# reflow_controller_v2_eagle7.net
KiCad netlist of a schematic drawn in EAGLE
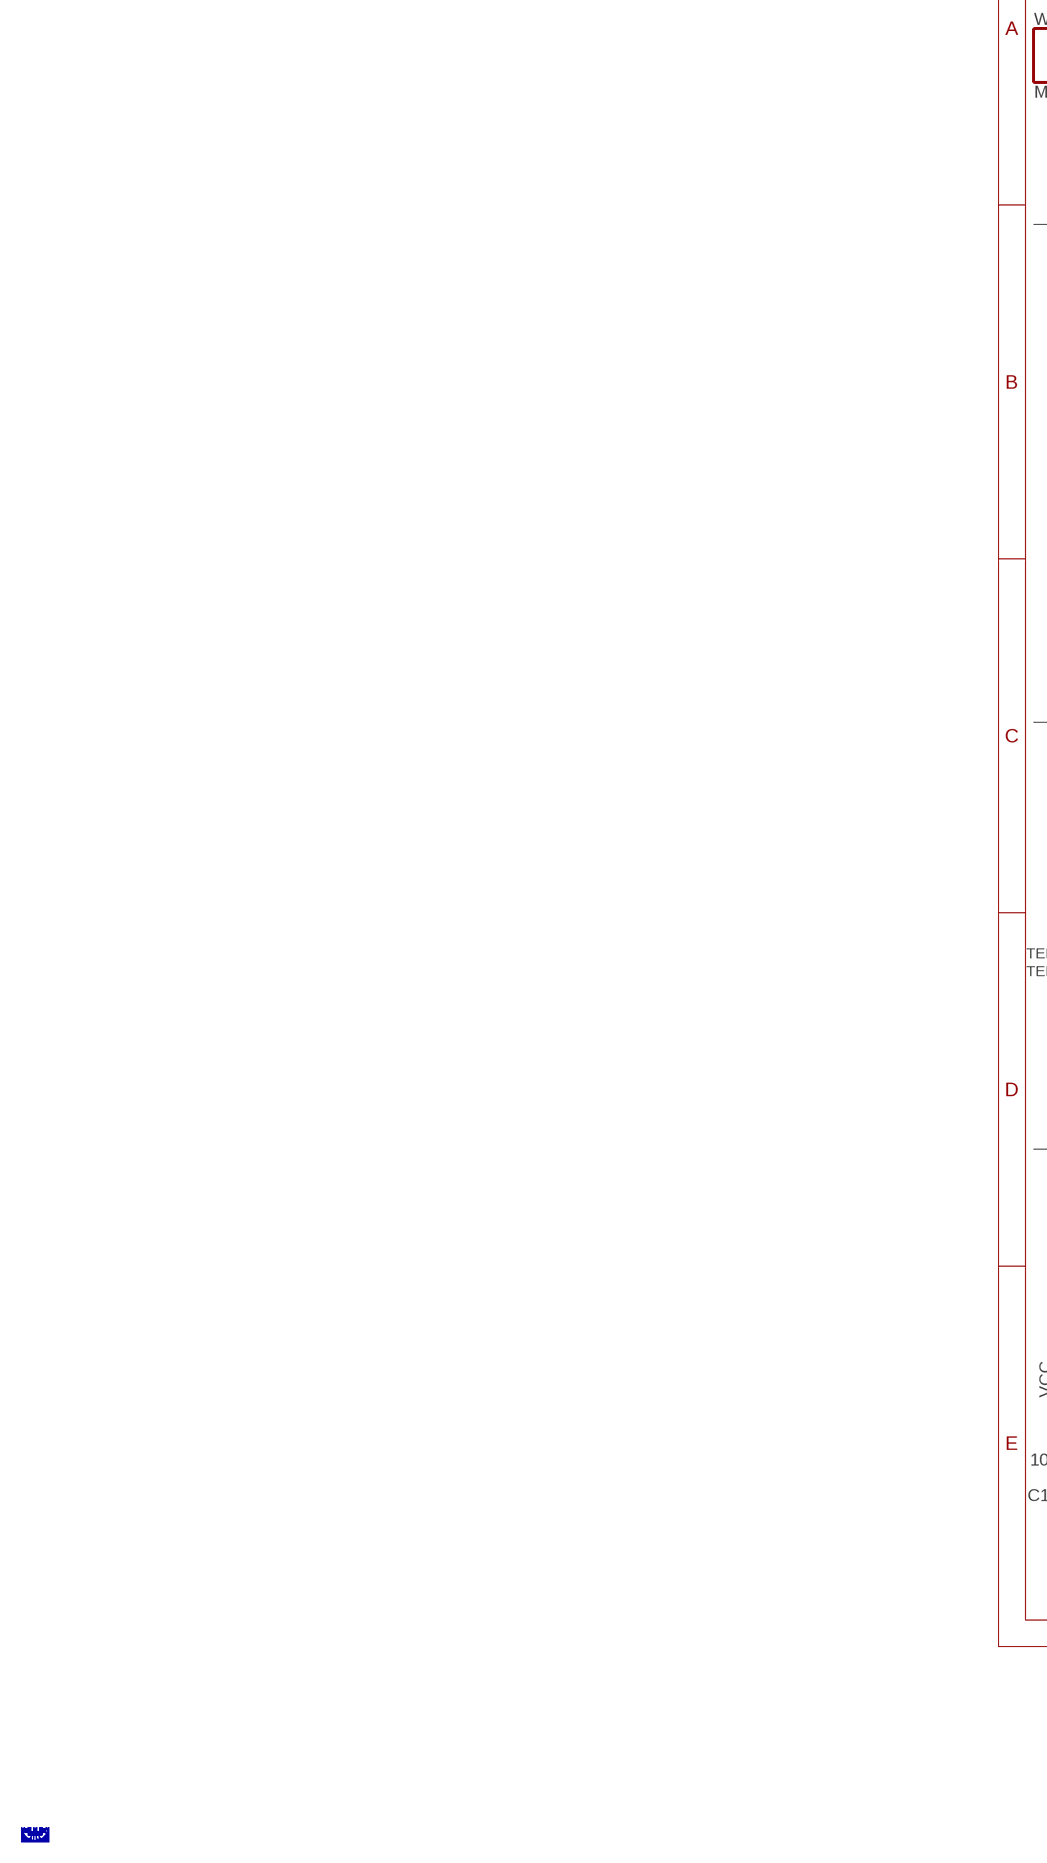
[diagram p0: schematic, sheet 1, part 1 of 2]
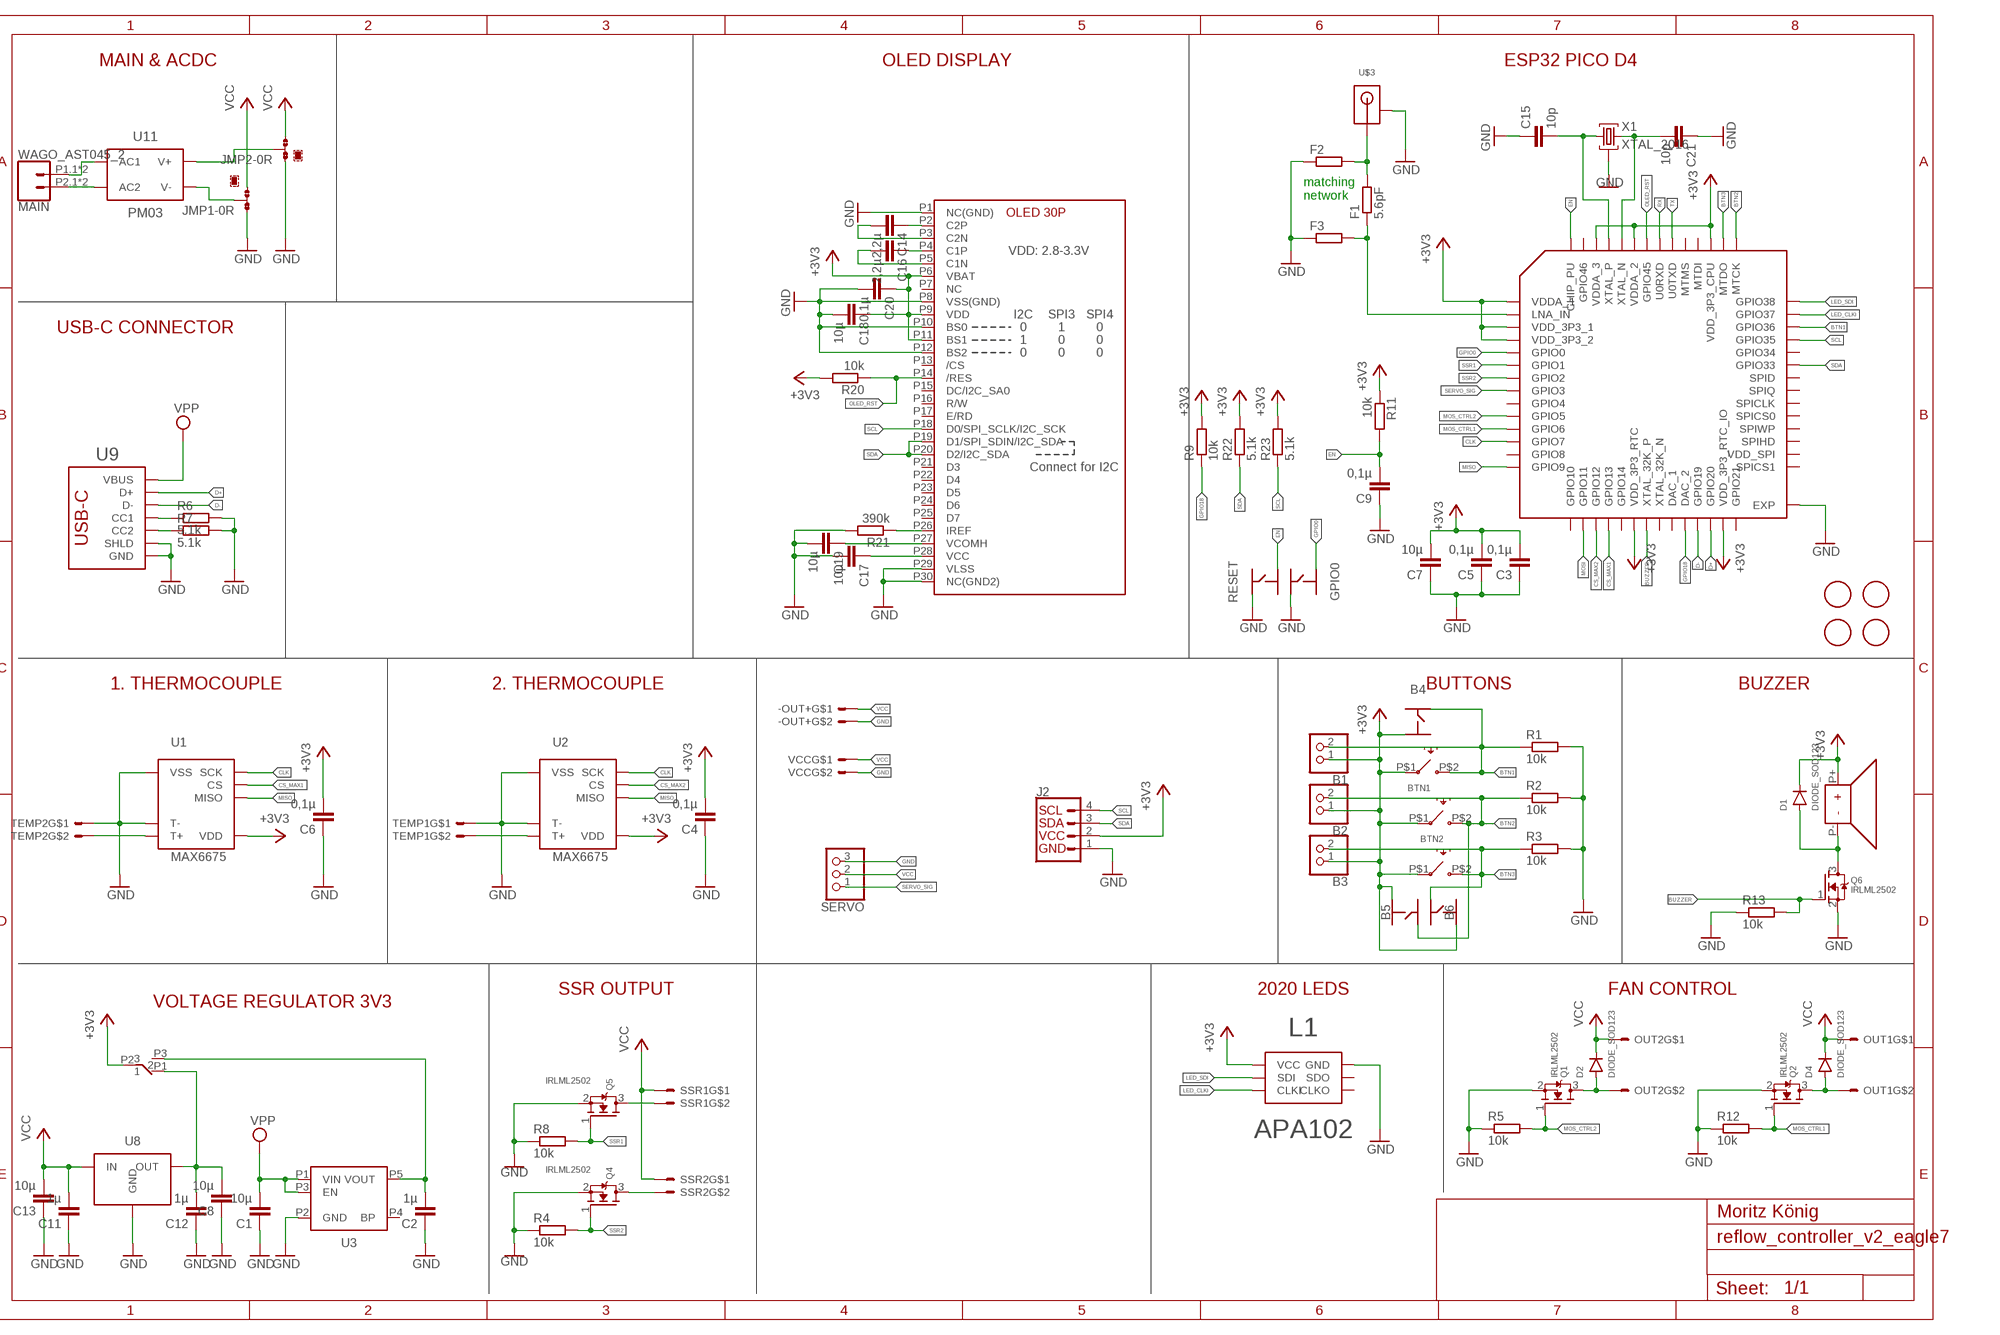
[diagram p1: schematic, sheet 1, part 2 of 2]

(export (version "E")
  (design (tool "Eeschema 10.0.6"))
  (components
    (comp (ref "-OUT+")
      (value "MOLEX_2MM_2P")
      (footprint "eagle-import:MOLEX_2MM_2P")
      (libsource (lib "eagle-import") (part "MOLEX_2MM_2P"))
    )
    (comp (ref "B1")
      (value "PINHD-1X02_2.00")
      (footprint "eagle-import:1X02M")
      (libsource (lib "eagle-import") (part "PINHD-1X02_2.00"))
    )
    (comp (ref "B2")
      (value "PINHD-1X02_2.00")
      (footprint "eagle-import:1X02M")
      (libsource (lib "eagle-import") (part "PINHD-1X02_2.00"))
    )
    (comp (ref "B3")
      (value "PINHD-1X02_2.00")
      (footprint "eagle-import:1X02M")
      (libsource (lib "eagle-import") (part "PINHD-1X02_2.00"))
    )
    (comp (ref "B4")
      (value "BUTTON_4PIN_TS-1070A")
      (footprint "eagle-import:BUTTON_WHITE_SMD")
      (libsource (lib "eagle-import") (part "BUTTON_4PIN_TS-1070A"))
    )
    (comp (ref "B5")
      (value "BUTTON_4PIN_TS-1070A")
      (footprint "eagle-import:BUTTON_WHITE_SMD")
      (libsource (lib "eagle-import") (part "BUTTON_4PIN_TS-1070A"))
    )
    (comp (ref "B6")
      (value "BUTTON_4PIN_TS-1070A")
      (footprint "eagle-import:BUTTON_WHITE_SMD")
      (libsource (lib "eagle-import") (part "BUTTON_4PIN_TS-1070A"))
    )
    (comp (ref "BTN1")
      (value "BUTTON_6X6_SILICON")
      (footprint "eagle-import:BUTTON_SILICON")
      (libsource (lib "eagle-import") (part "BUTTON_6X6_SILICON"))
    )
    (comp (ref "BTN2")
      (value "BUTTON_6X6_SILICON")
      (footprint "eagle-import:BUTTON_SILICON")
      (libsource (lib "eagle-import") (part "BUTTON_6X6_SILICON"))
    )
    (comp (ref "BTN3")
      (value "BUTTON_6X6_SILICON")
      (footprint "eagle-import:BUTTON_SILICON")
      (libsource (lib "eagle-import") (part "BUTTON_6X6_SILICON"))
    )
    (comp (ref "C1")
      (value "10µ")
      (footprint "eagle-import:C0603")
      (libsource (lib "eagle-import") (part "C-EU_WO_KEEPOUT"))
    )
    (comp (ref "C2")
      (value "1µ")
      (footprint "eagle-import:C0603")
      (libsource (lib "eagle-import") (part "C-EU_WO_KEEPOUT"))
    )
    (comp (ref "C3")
      (value "0,1µ")
      (footprint "eagle-import:C0603")
      (libsource (lib "eagle-import") (part "C-EU_WO_KEEPOUT"))
    )
    (comp (ref "C4")
      (value "0,1µ")
      (footprint "eagle-import:C0603")
      (libsource (lib "eagle-import") (part "C-EUC0603"))
    )
    (comp (ref "C5")
      (value "0,1µ")
      (footprint "eagle-import:C0603")
      (libsource (lib "eagle-import") (part "C-EU_WO_KEEPOUT"))
    )
    (comp (ref "C6")
      (value "0,1µ")
      (footprint "eagle-import:C0603")
      (libsource (lib "eagle-import") (part "C-EUC0603"))
    )
    (comp (ref "C7")
      (value "10µ")
      (footprint "eagle-import:C0603")
      (libsource (lib "eagle-import") (part "C-EU_WO_KEEPOUT"))
    )
    (comp (ref "C8")
      (value "10µ")
      (footprint "eagle-import:C0603")
      (libsource (lib "eagle-import") (part "C-EU_WO_KEEPOUT"))
    )
    (comp (ref "C9")
      (value "0,1µ")
      (footprint "eagle-import:C0603")
      (libsource (lib "eagle-import") (part "C-EU_WO_KEEPOUT"))
    )
    (comp (ref "C11")
      (value "1µ")
      (footprint "eagle-import:C0603")
      (libsource (lib "eagle-import") (part "C-EU_WO_KEEPOUT"))
    )
    (comp (ref "C12")
      (value "1µ")
      (footprint "eagle-import:C0603")
      (libsource (lib "eagle-import") (part "C-EU_WO_KEEPOUT"))
    )
    (comp (ref "C13")
      (value "10µ")
      (footprint "eagle-import:C0603")
      (libsource (lib "eagle-import") (part "C-EU_WO_KEEPOUT"))
    )
    (comp (ref "C14")
      (value "2,2µ")
      (footprint "eagle-import:C0603")
      (libsource (lib "eagle-import") (part "C-EU_WO_KEEPOUT"))
    )
    (comp (ref "C15")
      (value "10p")
      (footprint "eagle-import:C0603")
      (libsource (lib "eagle-import") (part "C-EU_WO_KEEPOUT"))
    )
    (comp (ref "C16")
      (value "2,2µ")
      (footprint "eagle-import:C0603")
      (libsource (lib "eagle-import") (part "C-EU_WO_KEEPOUT"))
    )
    (comp (ref "C17")
      (value "10µ")
      (footprint "eagle-import:C0603")
      (libsource (lib "eagle-import") (part "C-EU_WO_KEEPOUT"))
    )
    (comp (ref "C18")
      (value "10µ")
      (footprint "eagle-import:C0603")
      (libsource (lib "eagle-import") (part "C-EU_WO_KEEPOUT"))
    )
    (comp (ref "C19")
      (value "10µ")
      (footprint "eagle-import:C0603")
      (libsource (lib "eagle-import") (part "C-EU_WO_KEEPOUT"))
    )
    (comp (ref "C20")
      (value "0,1µ")
      (footprint "eagle-import:C0603")
      (libsource (lib "eagle-import") (part "C-EU_WO_KEEPOUT"))
    )
    (comp (ref "C21")
      (value "10p")
      (footprint "eagle-import:C0603")
      (libsource (lib "eagle-import") (part "C-EU_WO_KEEPOUT"))
    )
    (comp (ref "D1")
      (value "DIODE_SOD123")
      (footprint "eagle-import:SOD123")
      (libsource (lib "eagle-import") (part "DIODE_SOD123"))
    )
    (comp (ref "D2")
      (value "DIODE_SOD123")
      (footprint "eagle-import:SOD123")
      (libsource (lib "eagle-import") (part "DIODE_SOD123"))
    )
    (comp (ref "D4")
      (value "DIODE_SOD123")
      (footprint "eagle-import:SOD123")
      (libsource (lib "eagle-import") (part "DIODE_SOD123"))
    )
    (comp (ref "ESP")
      (value "ESP32_S2_QFN56_NEW")
      (footprint "eagle-import:QFN56_7X7")
      (libsource (lib "eagle-import") (part "ESP32_S2_QFN56_NEW"))
    )
    (comp (ref "F1")
      (value "5.6pF")
      (footprint "eagle-import:R0402")
      (libsource (lib "eagle-import") (part "R-EU-0402-WOKEEPOUT"))
    )
    (comp (ref "F2")
      (value "R-EU-0402-WOKEEPOUT")
      (footprint "eagle-import:R0402")
      (libsource (lib "eagle-import") (part "R-EU-0402-WOKEEPOUT"))
    )
    (comp (ref "F3")
      (value "R-EU-0402-WOKEEPOUT")
      (footprint "eagle-import:R0402")
      (libsource (lib "eagle-import") (part "R-EU-0402-WOKEEPOUT"))
    )
    (comp (ref "GPIO0")
      (value "BUTTON_4PIN_TS_1177")
      (footprint "eagle-import:TS-1177-C-B-B")
      (libsource (lib "eagle-import") (part "BUTTON_4PIN_TS_1177"))
    )
    (comp (ref "J2")
      (value "QWIIC_CONNECTORJS-1MM")
      (footprint "eagle-import:1X04_1MM_RA")
      (libsource (lib "eagle-import") (part "QWIIC_CONNECTORJS-1MM"))
    )
    (comp (ref "JMP1")
      (value "0R-JUMPA")
      (footprint "eagle-import:A0R-JMP")
      (libsource (lib "eagle-import") (part "0R-JUMPA"))
    )
    (comp (ref "JMP2")
      (value "0R-JUMPA")
      (footprint "eagle-import:A0R-JMP")
      (libsource (lib "eagle-import") (part "0R-JUMPA"))
    )
    (comp (ref "L1")
      (value "APA102_2020")
      (footprint "eagle-import:APA102_2020")
      (libsource (lib "eagle-import") (part "APA102_2020"))
    )
    (comp (ref "MAIN")
      (value "WAGO_AST045_2")
      (footprint "eagle-import:WAGO_AST045_2")
      (libsource (lib "eagle-import") (part "WAGO_AST045_2"))
    )
    (comp (ref "OUT1")
      (value "MOLEX_2MM_2P")
      (footprint "eagle-import:MOLEX_2MM_2P")
      (libsource (lib "eagle-import") (part "MOLEX_2MM_2P"))
    )
    (comp (ref "OUT2")
      (value "MOLEX_2MM_2P")
      (footprint "eagle-import:MOLEX_2MM_2P")
      (libsource (lib "eagle-import") (part "MOLEX_2MM_2P"))
    )
    (comp (ref "Q1")
      (value "IRLML2502")
      (footprint "eagle-import:SOT23")
      (libsource (lib "eagle-import") (part "IRLML2502"))
    )
    (comp (ref "Q2")
      (value "IRLML2502")
      (footprint "eagle-import:SOT23")
      (libsource (lib "eagle-import") (part "IRLML2502"))
    )
    (comp (ref "Q4")
      (value "IRLML2502")
      (footprint "eagle-import:SOT23")
      (libsource (lib "eagle-import") (part "IRLML2502"))
    )
    (comp (ref "Q5")
      (value "IRLML2502")
      (footprint "eagle-import:SOT23")
      (libsource (lib "eagle-import") (part "IRLML2502"))
    )
    (comp (ref "Q6")
      (value "IRLML2502")
      (footprint "eagle-import:SOT23")
      (libsource (lib "eagle-import") (part "IRLML2502"))
    )
    (comp (ref "R1")
      (value "10k")
      (footprint "eagle-import:R0603")
      (libsource (lib "eagle-import") (part "R-EU_WO_KEEPOUT"))
    )
    (comp (ref "R2")
      (value "10k")
      (footprint "eagle-import:R0603")
      (libsource (lib "eagle-import") (part "R-EU_WO_KEEPOUT"))
    )
    (comp (ref "R3")
      (value "10k")
      (footprint "eagle-import:R0603")
      (libsource (lib "eagle-import") (part "R-EU_WO_KEEPOUT"))
    )
    (comp (ref "R4")
      (value "10k")
      (footprint "eagle-import:R0603")
      (libsource (lib "eagle-import") (part "R-EU_WO_KEEPOUT"))
    )
    (comp (ref "R5")
      (value "10k")
      (footprint "eagle-import:R0603")
      (libsource (lib "eagle-import") (part "R-EU_WO_KEEPOUT"))
    )
    (comp (ref "R6")
      (value "5.1k")
      (footprint "eagle-import:R0603")
      (libsource (lib "eagle-import") (part "R-EU_WO_KEEPOUT"))
    )
    (comp (ref "R7")
      (value "5.1k")
      (footprint "eagle-import:R0603")
      (libsource (lib "eagle-import") (part "R-EU_WO_KEEPOUT"))
    )
    (comp (ref "R8")
      (value "10k")
      (footprint "eagle-import:R0603")
      (libsource (lib "eagle-import") (part "R-EU_WO_KEEPOUT"))
    )
    (comp (ref "R9")
      (value "10k")
      (footprint "eagle-import:R0603")
      (libsource (lib "eagle-import") (part "R-EU_WO_KEEPOUT"))
    )
    (comp (ref "R11")
      (value "10k")
      (footprint "eagle-import:R0603")
      (libsource (lib "eagle-import") (part "R-EU_WO_KEEPOUT"))
    )
    (comp (ref "R12")
      (value "10k")
      (footprint "eagle-import:R0603")
      (libsource (lib "eagle-import") (part "R-EU_WO_KEEPOUT"))
    )
    (comp (ref "R13")
      (value "10k")
      (footprint "eagle-import:R0603")
      (libsource (lib "eagle-import") (part "R-EU_WO_KEEPOUT"))
    )
    (comp (ref "R20")
      (value "10k")
      (footprint "eagle-import:R0603")
      (libsource (lib "eagle-import") (part "R-EU_WO_KEEPOUT"))
    )
    (comp (ref "R21")
      (value "390k")
      (footprint "eagle-import:R0603")
      (libsource (lib "eagle-import") (part "R-EU_WO_KEEPOUT"))
    )
    (comp (ref "R22")
      (value "5.1k")
      (footprint "eagle-import:R0603")
      (libsource (lib "eagle-import") (part "R-EU_WO_KEEPOUT"))
    )
    (comp (ref "R23")
      (value "5.1k")
      (footprint "eagle-import:R0603")
      (libsource (lib "eagle-import") (part "R-EU_WO_KEEPOUT"))
    )
    (comp (ref "RESET")
      (value "BUTTON_4PIN_TS_1177")
      (footprint "eagle-import:TS-1177-C-B-B")
      (libsource (lib "eagle-import") (part "BUTTON_4PIN_TS_1177"))
    )
    (comp (ref "S1")
      (value "SWITCH_MS-22C01-G010")
      (footprint "eagle-import:MS-22C01-G010")
      (libsource (lib "eagle-import") (part "SWITCH_MS-22C01-G010"))
    )
    (comp (ref "SERVO")
      (value "PINHD-1X03_2.54")
      (footprint "eagle-import:1X03")
      (libsource (lib "eagle-import") (part "PINHD-1X03_2.54"))
    )
    (comp (ref "SSR1")
      (value "MOLEX_2MM_2P")
      (footprint "eagle-import:MOLEX_2MM_2P")
      (libsource (lib "eagle-import") (part "MOLEX_2MM_2P"))
    )
    (comp (ref "SSR2")
      (value "MOLEX_2MM_2P")
      (footprint "eagle-import:MOLEX_2MM_2P")
      (libsource (lib "eagle-import") (part "MOLEX_2MM_2P"))
    )
    (comp (ref "TEMP1")
      (value "MOLEX_2MM_2P")
      (footprint "eagle-import:MOLEX_2MM_2P")
      (libsource (lib "eagle-import") (part "MOLEX_2MM_2P"))
    )
    (comp (ref "TEMP2")
      (value "MOLEX_2MM_2P")
      (footprint "eagle-import:MOLEX_2MM_2P")
      (libsource (lib "eagle-import") (part "MOLEX_2MM_2P"))
    )
    (comp (ref "U$1")
      (value "FIDUCIAL")
      (footprint "eagle-import:FIDUCIAL_1MM")
      (libsource (lib "eagle-import") (part "FIDUCIAL"))
    )
    (comp (ref "U$2")
      (value "FIDUCIAL")
      (footprint "eagle-import:FIDUCIAL_1MM")
      (libsource (lib "eagle-import") (part "FIDUCIAL"))
    )
    (comp (ref "U$3")
      (value "UFL_ANT_CONNECTOR")
      (footprint "eagle-import:UFL_ANT_CONNECTOR")
      (libsource (lib "eagle-import") (part "UFL_ANT_CONNECTOR"))
    )
    (comp (ref "U$4")
      (value "FIDUCIAL")
      (footprint "eagle-import:FIDUCIAL_1MM")
      (libsource (lib "eagle-import") (part "FIDUCIAL"))
    )
    (comp (ref "U$5")
      (value "FIDUCIAL")
      (footprint "eagle-import:FIDUCIAL_1MM")
      (libsource (lib "eagle-import") (part "FIDUCIAL"))
    )
    (comp (ref "U1")
      (value "MAX6675")
      (footprint "eagle-import:SO8")
      (libsource (lib "eagle-import") (part "MAX6675"))
    )
    (comp (ref "U2")
      (value "MAX6675")
      (footprint "eagle-import:SO8")
      (libsource (lib "eagle-import") (part "MAX6675"))
    )
    (comp (ref "U3")
      (value "RT9193_SC70-5")
      (footprint "eagle-import:SC-70-5")
      (libsource (lib "eagle-import") (part "RT9193_SC70-5"))
    )
    (comp (ref "U4")
      (value "OLD_096_SSD1306_30P_2B")
      (footprint "eagle-import:OLED_096_30P_B")
      (libsource (lib "eagle-import") (part "OLD_096_SSD1306_30P_2B"))
    )
    (comp (ref "U8")
      (value "LM1117")
      (footprint "eagle-import:SOT223")
      (libsource (lib "eagle-import") (part "LM1117"))
    )
    (comp (ref "U9")
      (value "USB_C_C393939")
      (footprint "eagle-import:USBC_C393939")
      (libsource (lib "eagle-import") (part "USB_C_C393939"))
    )
    (comp (ref "U10")
      (value "MLT-5030-BUZZER")
      (footprint "eagle-import:MLT-5030-BUZZER")
      (libsource (lib "eagle-import") (part "MLT-5030-BUZZER"))
    )
    (comp (ref "U11")
      (value "HILINK_PM03")
      (footprint "eagle-import:HILINK_PM03")
      (libsource (lib "eagle-import") (part "HILINK_PM03"))
    )
    (comp (ref "VCC")
      (value "MOLEX_2MM_2P")
      (footprint "eagle-import:MOLEX_2MM_2P")
      (libsource (lib "eagle-import") (part "MOLEX_2MM_2P"))
    )
    (comp (ref "X1")
      (value "XTAL_2016")
      (footprint "eagle-import:XTYL_2016")
      (libsource (lib "eagle-import") (part "XTAL_2016"))
    )
  )
  (nets
    (net (code "1") (name "+3V3") (class "Default")
      (node (ref "B1") (pin "1") (pinfunction "1_1") (pintype "passive"))
      (node (ref "B2") (pin "1") (pinfunction "1_1") (pintype "passive"))
      (node (ref "B3") (pin "1") (pinfunction "1_1") (pintype "passive"))
      (node (ref "B4") (pin "P$2") (pinfunction "3_P$2") (pintype "bidirectional"))
      (node (ref "B5") (pin "P$2") (pinfunction "3_P$2") (pintype "bidirectional"))
      (node (ref "B6") (pin "P$2") (pinfunction "3_P$2") (pintype "bidirectional"))
      (node (ref "BTN1") (pin "P$1") (pinfunction "P1_P$1") (pintype "bidirectional"))
      (node (ref "BTN2") (pin "P$1") (pinfunction "P1_P$1") (pintype "bidirectional"))
      (node (ref "BTN3") (pin "P$1") (pinfunction "P1_P$1") (pintype "bidirectional"))
      (node (ref "C18") (pin "1") (pinfunction "1_1") (pintype "passive"))
      (node (ref "C20") (pin "1") (pinfunction "1_1") (pintype "passive"))
      (node (ref "C3") (pin "2") (pinfunction "2_2") (pintype "passive"))
      (node (ref "C4") (pin "2") (pinfunction "2_2") (pintype "passive"))
      (node (ref "C5") (pin "2") (pinfunction "2_2") (pintype "passive"))
      (node (ref "C6") (pin "2") (pinfunction "2_2") (pintype "passive"))
      (node (ref "C7") (pin "2") (pinfunction "2_2") (pintype "passive"))
      (node (ref "D1") (pin "P$2") (pinfunction "C_P$2") (pintype "passive"))
      (node (ref "ESP") (pin "1") (pinfunction "VDDA_1_1") (pintype "bidirectional"))
      (node (ref "ESP") (pin "20") (pinfunction "VDD_3P3_RTC_20") (pintype "bidirectional"))
      (node (ref "ESP") (pin "27") (pinfunction "VDD_3P3_RTC_IO_27") (pintype "bidirectional"))
      (node (ref "ESP") (pin "3") (pinfunction "VDD_3P3_1_3") (pintype "bidirectional"))
      (node (ref "ESP") (pin "4") (pinfunction "VDD_3P3_2_4") (pintype "bidirectional"))
      (node (ref "ESP") (pin "45") (pinfunction "VDD_3P3_CPU_45") (pintype "bidirectional"))
      (node (ref "ESP") (pin "51") (pinfunction "VDDA_2_51") (pintype "bidirectional"))
      (node (ref "ESP") (pin "54") (pinfunction "VDDA_3_54") (pintype "bidirectional"))
      (node (ref "J2") (pin "2") (pinfunction "VCC_2") (pintype "power_in"))
      (node (ref "L1") (pin "P1") (pinfunction "VCC_P1") (pintype "bidirectional"))
      (node (ref "L1") (pin "P1.1") (pinfunction "VCC_P1.1") (pintype "bidirectional"))
      (node (ref "R11") (pin "1") (pinfunction "1_1") (pintype "passive"))
      (node (ref "R20") (pin "2") (pinfunction "2_2") (pintype "passive"))
      (node (ref "R22") (pin "2") (pinfunction "2_2") (pintype "passive"))
      (node (ref "R23") (pin "2") (pinfunction "2_2") (pintype "passive"))
      (node (ref "R9") (pin "2") (pinfunction "2_2") (pintype "passive"))
      (node (ref "S1") (pin "P2") (pinfunction "2_P2") (pintype "bidirectional"))
      (node (ref "U1") (pin "4") (pinfunction "VDD_4") (pintype "bidirectional"))
      (node (ref "U10") (pin "P+") (pinfunction "P+_P+") (pintype "bidirectional"))
      (node (ref "U2") (pin "4") (pinfunction "VDD_4") (pintype "bidirectional"))
      (node (ref "U4") (pin "P11") (pinfunction "BS1_P11") (pintype "bidirectional"))
      (node (ref "U4") (pin "P6") (pinfunction "VBAT_P6") (pintype "bidirectional"))
      (node (ref "U4") (pin "P9") (pinfunction "VDD_P9") (pintype "bidirectional"))
    )
    (net (code "2") (name "BTN1") (class "Default")
      (node (ref "B1") (pin "2") (pinfunction "2_2") (pintype "passive"))
      (node (ref "B4") (pin "P$4") (pinfunction "2_P$4") (pintype "bidirectional"))
      (node (ref "BTN1") (pin "P$2") (pinfunction "P2_P$2") (pintype "bidirectional"))
      (node (ref "ESP") (pin "40") (pinfunction "GPIO36_40") (pintype "bidirectional"))
      (node (ref "R1") (pin "1") (pinfunction "1_1") (pintype "passive"))
    )
    (net (code "3") (name "BTN2") (class "Default")
      (node (ref "B2") (pin "2") (pinfunction "2_2") (pintype "passive"))
      (node (ref "B5") (pin "P$4") (pinfunction "2_P$4") (pintype "bidirectional"))
      (node (ref "BTN2") (pin "P$2") (pinfunction "P2_P$2") (pintype "bidirectional"))
      (node (ref "ESP") (pin "43") (pinfunction "MTCK_43") (pintype "bidirectional"))
      (node (ref "R2") (pin "1") (pinfunction "1_1") (pintype "passive"))
    )
    (net (code "4") (name "BTN3") (class "Default")
      (node (ref "B3") (pin "2") (pinfunction "2_2") (pintype "passive"))
      (node (ref "B6") (pin "P$4") (pinfunction "2_P$4") (pintype "bidirectional"))
      (node (ref "BTN3") (pin "P$2") (pinfunction "P2_P$2") (pintype "bidirectional"))
      (node (ref "ESP") (pin "44") (pinfunction "MTDO_44") (pintype "bidirectional"))
      (node (ref "R3") (pin "1") (pinfunction "1_1") (pintype "passive"))
    )
    (net (code "5") (name "BUZZER") (class "Default")
      (node (ref "ESP") (pin "21") (pinfunction "XTAL_32K_P_21") (pintype "bidirectional"))
      (node (ref "Q6") (pin "1") (pinfunction "G_1") (pintype "bidirectional"))
      (node (ref "R13") (pin "2") (pinfunction "2_2") (pintype "passive"))
    )
    (net (code "6") (name "CLK") (class "Default")
      (node (ref "ESP") (pin "12") (pinfunction "GPIO7_12") (pintype "bidirectional"))
      (node (ref "U1") (pin "5") (pinfunction "SCK_5") (pintype "bidirectional"))
      (node (ref "U2") (pin "5") (pinfunction "SCK_5") (pintype "bidirectional"))
    )
    (net (code "7") (name "CS_MAX1") (class "Default")
      (node (ref "ESP") (pin "18") (pinfunction "GPIO13_18") (pintype "bidirectional"))
      (node (ref "U1") (pin "6") (pinfunction "CS_6") (pintype "bidirectional"))
    )
    (net (code "8") (name "CS_MAX2") (class "Default")
      (node (ref "ESP") (pin "17") (pinfunction "GPIO12_17") (pintype "bidirectional"))
      (node (ref "U2") (pin "6") (pinfunction "CS_6") (pintype "bidirectional"))
    )
    (net (code "9") (name "D+") (class "Default")
      (node (ref "ESP") (pin "26") (pinfunction "GPIO20_26") (pintype "bidirectional"))
      (node (ref "U9") (pin "A6") (pinfunction "D+_A6") (pintype "bidirectional"))
      (node (ref "U9") (pin "B6") (pinfunction "D+_B6") (pintype "bidirectional"))
    )
    (net (code "10") (name "D-") (class "Default")
      (node (ref "ESP") (pin "25") (pinfunction "GPIO19_25") (pintype "bidirectional"))
      (node (ref "U9") (pin "A7") (pinfunction "D-_A7") (pintype "bidirectional"))
      (node (ref "U9") (pin "B7") (pinfunction "D-_B7") (pintype "bidirectional"))
    )
    (net (code "11") (name "EN") (class "Default")
      (node (ref "C9") (pin "2") (pinfunction "2_2") (pintype "passive"))
      (node (ref "ESP") (pin "56") (pinfunction "CHIP_PU_56") (pintype "bidirectional"))
      (node (ref "R11") (pin "2") (pinfunction "2_2") (pintype "passive"))
      (node (ref "RESET") (pin "P4") (pinfunction "4_P4") (pintype "bidirectional"))
    )
    (net (code "12") (name "GND") (class "Default")
      (node (ref "-OUT+") (pin "2") (pinfunction "S_2") (pintype "passive"))
      (node (ref "C1") (pin "1") (pinfunction "1_1") (pintype "passive"))
      (node (ref "C11") (pin "1") (pinfunction "1_1") (pintype "passive"))
      (node (ref "C12") (pin "1") (pinfunction "1_1") (pintype "passive"))
      (node (ref "C13") (pin "1") (pinfunction "1_1") (pintype "passive"))
      (node (ref "C15") (pin "1") (pinfunction "1_1") (pintype "passive"))
      (node (ref "C17") (pin "2") (pinfunction "2_2") (pintype "passive"))
      (node (ref "C18") (pin "2") (pinfunction "2_2") (pintype "passive"))
      (node (ref "C19") (pin "2") (pinfunction "2_2") (pintype "passive"))
      (node (ref "C2") (pin "1") (pinfunction "1_1") (pintype "passive"))
      (node (ref "C20") (pin "2") (pinfunction "2_2") (pintype "passive"))
      (node (ref "C21") (pin "1") (pinfunction "1_1") (pintype "passive"))
      (node (ref "C3") (pin "1") (pinfunction "1_1") (pintype "passive"))
      (node (ref "C4") (pin "1") (pinfunction "1_1") (pintype "passive"))
      (node (ref "C5") (pin "1") (pinfunction "1_1") (pintype "passive"))
      (node (ref "C6") (pin "1") (pinfunction "1_1") (pintype "passive"))
      (node (ref "C7") (pin "1") (pinfunction "1_1") (pintype "passive"))
      (node (ref "C8") (pin "1") (pinfunction "1_1") (pintype "passive"))
      (node (ref "C9") (pin "1") (pinfunction "1_1") (pintype "passive"))
      (node (ref "ESP") (pin "57") (pinfunction "EXP_57") (pintype "bidirectional"))
      (node (ref "F2") (pin "1") (pinfunction "1_1") (pintype "passive"))
      (node (ref "F3") (pin "1") (pinfunction "1_1") (pintype "passive"))
      (node (ref "GPIO0") (pin "P1") (pinfunction "1_P1") (pintype "bidirectional"))
      (node (ref "J2") (pin "1") (pinfunction "GND_1") (pintype "power_in"))
      (node (ref "JMP1") (pin "1") (pinfunction "1_1") (pintype "passive"))
      (node (ref "JMP2") (pin "1") (pinfunction "1_1") (pintype "passive"))
      (node (ref "L1") (pin "P6") (pinfunction "GND_P6") (pintype "bidirectional"))
      (node (ref "L1") (pin "P6.1") (pinfunction "GND_P6.1") (pintype "bidirectional"))
      (node (ref "Q1") (pin "2") (pinfunction "S_2") (pintype "bidirectional"))
      (node (ref "Q2") (pin "2") (pinfunction "S_2") (pintype "bidirectional"))
      (node (ref "Q4") (pin "2") (pinfunction "S_2") (pintype "bidirectional"))
      (node (ref "Q5") (pin "2") (pinfunction "S_2") (pintype "bidirectional"))
      (node (ref "Q6") (pin "2") (pinfunction "S_2") (pintype "bidirectional"))
      (node (ref "R1") (pin "2") (pinfunction "2_2") (pintype "passive"))
      (node (ref "R12") (pin "1") (pinfunction "1_1") (pintype "passive"))
      (node (ref "R13") (pin "1") (pinfunction "1_1") (pintype "passive"))
      (node (ref "R2") (pin "2") (pinfunction "2_2") (pintype "passive"))
      (node (ref "R21") (pin "2") (pinfunction "2_2") (pintype "passive"))
      (node (ref "R3") (pin "2") (pinfunction "2_2") (pintype "passive"))
      (node (ref "R4") (pin "1") (pinfunction "1_1") (pintype "passive"))
      (node (ref "R5") (pin "1") (pinfunction "1_1") (pintype "passive"))
      (node (ref "R6") (pin "2") (pinfunction "2_2") (pintype "passive"))
      (node (ref "R7") (pin "2") (pinfunction "2_2") (pintype "passive"))
      (node (ref "R8") (pin "1") (pinfunction "1_1") (pintype "passive"))
      (node (ref "RESET") (pin "P1") (pinfunction "1_P1") (pintype "bidirectional"))
      (node (ref "SERVO") (pin "3") (pinfunction "3_3") (pintype "passive"))
      (node (ref "TEMP1") (pin "1") (pinfunction "S_1") (pintype "passive"))
      (node (ref "TEMP2") (pin "1") (pinfunction "S_1") (pintype "passive"))
      (node (ref "U$3") (pin "P1.-") (pinfunction "GND_P1.-") (pintype "bidirectional"))
      (node (ref "U$3") (pin "P2.-") (pinfunction "GND_P2.-") (pintype "bidirectional"))
      (node (ref "U1") (pin "1") (pinfunction "VSS_1") (pintype "bidirectional"))
      (node (ref "U1") (pin "2") (pinfunction "T-_2") (pintype "bidirectional"))
      (node (ref "U2") (pin "1") (pinfunction "VSS_1") (pintype "bidirectional"))
      (node (ref "U2") (pin "2") (pinfunction "T-_2") (pintype "bidirectional"))
      (node (ref "U3") (pin "P2") (pinfunction "GND_P2") (pintype "bidirectional"))
      (node (ref "U4") (pin "P1") (pinfunction "NC(GND)_P1") (pintype "bidirectional"))
      (node (ref "U4") (pin "P10") (pinfunction "BS0_P10") (pintype "bidirectional"))
      (node (ref "U4") (pin "P12") (pinfunction "BS2_P12") (pintype "bidirectional"))
      (node (ref "U4") (pin "P29") (pinfunction "VLSS_P29") (pintype "bidirectional"))
      (node (ref "U4") (pin "P30") (pinfunction "NC(GND2)_P30") (pintype "bidirectional"))
      (node (ref "U4") (pin "P8") (pinfunction "VSS(GND)_P8") (pintype "bidirectional"))
      (node (ref "U8") (pin "1") (pinfunction "GND_1") (pintype "bidirectional"))
      (node (ref "U9") (pin "A1B12") (pinfunction "GND_A1B12") (pintype "bidirectional"))
      (node (ref "U9") (pin "B1A12") (pinfunction "GND_B1A12") (pintype "bidirectional"))
      (node (ref "U9") (pin "S1") (pinfunction "SHLD_S1") (pintype "bidirectional"))
      (node (ref "U9") (pin "S2") (pinfunction "SHLD_S2") (pintype "bidirectional"))
      (node (ref "U9") (pin "S3") (pinfunction "SHLD_S3") (pintype "bidirectional"))
      (node (ref "U9") (pin "S4") (pinfunction "SHLD_S4") (pintype "bidirectional"))
      (node (ref "VCC") (pin "2") (pinfunction "S_2") (pintype "passive"))
      (node (ref "X1") (pin "P2") (pinfunction "G_P2") (pintype "passive"))
      (node (ref "X1") (pin "P4") (pinfunction "G_P4") (pintype "passive"))
    )
    (net (code "13") (name "GPIO0") (class "Default")
      (node (ref "ESP") (pin "5") (pinfunction "GPIO0_5") (pintype "bidirectional"))
      (node (ref "GPIO0") (pin "P4") (pinfunction "4_P4") (pintype "bidirectional"))
    )
    (net (code "14") (name "GPIO18") (class "Default")
      (node (ref "ESP") (pin "24") (pinfunction "DAC_2_24") (pintype "bidirectional"))
      (node (ref "R9") (pin "1") (pinfunction "1_1") (pintype "passive"))
    )
    (net (code "15") (name "LED_CLKI") (class "Default")
      (node (ref "ESP") (pin "41") (pinfunction "GPIO37_41") (pintype "bidirectional"))
      (node (ref "L1") (pin "P5") (pinfunction "CLKI_P5") (pintype "bidirectional"))
    )
    (net (code "16") (name "LED_SDI") (class "Default")
      (node (ref "ESP") (pin "42") (pinfunction "GPIO38_42") (pintype "bidirectional"))
      (node (ref "L1") (pin "P4") (pinfunction "SDI_P4") (pintype "bidirectional"))
    )
    (net (code "17") (name "MISO") (class "Default")
      (node (ref "ESP") (pin "14") (pinfunction "GPIO9_14") (pintype "bidirectional"))
      (node (ref "U1") (pin "7") (pinfunction "MISO_7") (pintype "bidirectional"))
      (node (ref "U2") (pin "7") (pinfunction "MISO_7") (pintype "bidirectional"))
    )
    (net (code "18") (name "MOSI") (class "Default")
      (node (ref "ESP") (pin "16") (pinfunction "GPIO11_16") (pintype "bidirectional"))
    )
    (net (code "19") (name "MOS_CTRL1") (class "Default")
      (node (ref "ESP") (pin "11") (pinfunction "GPIO6_11") (pintype "bidirectional"))
      (node (ref "Q2") (pin "1") (pinfunction "G_1") (pintype "bidirectional"))
      (node (ref "R12") (pin "2") (pinfunction "2_2") (pintype "passive"))
    )
    (net (code "20") (name "MOS_CTRL2") (class "Default")
      (node (ref "ESP") (pin "10") (pinfunction "GPIO5_10") (pintype "bidirectional"))
      (node (ref "Q1") (pin "1") (pinfunction "G_1") (pintype "bidirectional"))
      (node (ref "R5") (pin "2") (pinfunction "2_2") (pintype "passive"))
    )
    (net (code "21") (name "Net-(D1-A)") (class "Default")
      (node (ref "D1") (pin "P$1") (pinfunction "A_P$1") (pintype "passive"))
      (node (ref "Q6") (pin "3") (pinfunction "D_3") (pintype "bidirectional"))
      (node (ref "U10") (pin "P-") (pinfunction "P-_P-") (pintype "bidirectional"))
    )
    (net (code "22") (name "Net-(D2-A)") (class "Default")
      (node (ref "D2") (pin "P$1") (pinfunction "A_P$1") (pintype "passive"))
      (node (ref "OUT2") (pin "2") (pinfunction "S_2") (pintype "passive"))
      (node (ref "Q1") (pin "3") (pinfunction "D_3") (pintype "bidirectional"))
    )
    (net (code "23") (name "Net-(D4-A)") (class "Default")
      (node (ref "D4") (pin "P$1") (pinfunction "A_P$1") (pintype "passive"))
      (node (ref "OUT1") (pin "2") (pinfunction "S_2") (pintype "passive"))
      (node (ref "Q2") (pin "3") (pinfunction "D_3") (pintype "bidirectional"))
    )
    (net (code "24") (name "Net-(ESP-LNA_IN)") (class "Default")
      (node (ref "ESP") (pin "2") (pinfunction "LNA_IN_2") (pintype "bidirectional"))
      (node (ref "F1") (pin "1") (pinfunction "1_1") (pintype "passive"))
      (node (ref "F3") (pin "2") (pinfunction "2_2") (pintype "passive"))
    )
    (net (code "25") (name "Net-(ESP-XTAL_N)") (class "Default")
      (node (ref "C21") (pin "2") (pinfunction "2_2") (pintype "passive"))
      (node (ref "ESP") (pin "52") (pinfunction "XTAL_N_52") (pintype "bidirectional"))
      (node (ref "X1") (pin "P3") (pinfunction "2_P3") (pintype "passive"))
    )
    (net (code "26") (name "Net-(ESP-XTAL_P)") (class "Default")
      (node (ref "C15") (pin "2") (pinfunction "2_2") (pintype "passive"))
      (node (ref "ESP") (pin "53") (pinfunction "XTAL_P_53") (pintype "bidirectional"))
      (node (ref "X1") (pin "P1") (pinfunction "1_P1") (pintype "passive"))
    )
    (net (code "27") (name "Net-(F1-Pad2)") (class "Default")
      (node (ref "F1") (pin "2") (pinfunction "2_2") (pintype "passive"))
      (node (ref "F2") (pin "2") (pinfunction "2_2") (pintype "passive"))
      (node (ref "U$3") (pin "ANT") (pinfunction "ANT_ANT") (pintype "bidirectional"))
    )
    (net (code "28") (name "Net-(JMP1-Pad2)") (class "Default")
      (node (ref "JMP1") (pin "2") (pinfunction "2_2") (pintype "passive"))
      (node (ref "U11") (pin "V-") (pinfunction "V-_V-") (pintype "bidirectional"))
    )
    (net (code "29") (name "Net-(JMP2-Pad2)") (class "Default")
      (node (ref "JMP2") (pin "2") (pinfunction "2_2") (pintype "passive"))
      (node (ref "U11") (pin "V+") (pinfunction "V+_V+") (pintype "bidirectional"))
    )
    (net (code "30") (name "Net-(MAIN-1-PadP1.1)") (class "Default")
      (node (ref "MAIN") (pin "P1.1") (pinfunction "1_P1.1") (pintype "passive"))
      (node (ref "MAIN") (pin "P1.2") (pinfunction "1_P1.2") (pintype "passive"))
      (node (ref "U11") (pin "AC1") (pinfunction "AC1_AC1") (pintype "bidirectional"))
    )
    (net (code "31") (name "Net-(MAIN-2-PadP2.1)") (class "Default")
      (node (ref "MAIN") (pin "P2.1") (pinfunction "2_P2.1") (pintype "passive"))
      (node (ref "MAIN") (pin "P2.2") (pinfunction "2_P2.2") (pintype "passive"))
      (node (ref "U11") (pin "AC2") (pinfunction "AC2_AC2") (pintype "bidirectional"))
    )
    (net (code "32") (name "Net-(Q4-D)") (class "Default")
      (node (ref "Q4") (pin "3") (pinfunction "D_3") (pintype "bidirectional"))
      (node (ref "SSR2") (pin "2") (pinfunction "S_2") (pintype "passive"))
    )
    (net (code "33") (name "Net-(Q5-D)") (class "Default")
      (node (ref "Q5") (pin "3") (pinfunction "D_3") (pintype "bidirectional"))
      (node (ref "SSR1") (pin "2") (pinfunction "S_2") (pintype "passive"))
    )
    (net (code "34") (name "Net-(S1-1)") (class "Default")
      (node (ref "C12") (pin "2") (pinfunction "2_2") (pintype "passive"))
      (node (ref "C8") (pin "2") (pinfunction "2_2") (pintype "passive"))
      (node (ref "S1") (pin "P1") (pinfunction "1_P1") (pintype "bidirectional"))
      (node (ref "U8") (pin "2") (pinfunction "OUT_2") (pintype "bidirectional"))
      (node (ref "U8") (pin "4") (pinfunction "OUT_4") (pintype "bidirectional"))
    )
    (net (code "35") (name "Net-(S1-3)") (class "Default")
      (node (ref "C2") (pin "2") (pinfunction "2_2") (pintype "passive"))
      (node (ref "S1") (pin "P3") (pinfunction "3_P3") (pintype "bidirectional"))
      (node (ref "U3") (pin "P5") (pinfunction "VOUT_P5") (pintype "bidirectional"))
    )
    (net (code "36") (name "Net-(TEMP1B-S)") (class "Default")
      (node (ref "TEMP1") (pin "2") (pinfunction "S_2") (pintype "passive"))
      (node (ref "U2") (pin "3") (pinfunction "T+_3") (pintype "bidirectional"))
    )
    (net (code "37") (name "Net-(TEMP2B-S)") (class "Default")
      (node (ref "TEMP2") (pin "2") (pinfunction "S_2") (pintype "passive"))
      (node (ref "U1") (pin "3") (pinfunction "T+_3") (pintype "bidirectional"))
    )
    (net (code "38") (name "Net-(U4-C1N)") (class "Default")
      (node (ref "C16") (pin "2") (pinfunction "2_2") (pintype "passive"))
      (node (ref "U4") (pin "P5") (pinfunction "C1N_P5") (pintype "bidirectional"))
    )
    (net (code "39") (name "Net-(U4-C1P)") (class "Default")
      (node (ref "C16") (pin "1") (pinfunction "1_1") (pintype "passive"))
      (node (ref "U4") (pin "P4") (pinfunction "C1P_P4") (pintype "bidirectional"))
    )
    (net (code "40") (name "Net-(U4-C2N)") (class "Default")
      (node (ref "C14") (pin "2") (pinfunction "2_2") (pintype "passive"))
      (node (ref "U4") (pin "P3") (pinfunction "C2N_P3") (pintype "bidirectional"))
    )
    (net (code "41") (name "Net-(U4-C2P)") (class "Default")
      (node (ref "C14") (pin "1") (pinfunction "1_1") (pintype "passive"))
      (node (ref "U4") (pin "P2") (pinfunction "C2P_P2") (pintype "bidirectional"))
    )
    (net (code "42") (name "Net-(U4-IREF)") (class "Default")
      (node (ref "R21") (pin "1") (pinfunction "1_1") (pintype "passive"))
      (node (ref "U4") (pin "P26") (pinfunction "IREF_P26") (pintype "bidirectional"))
    )
    (net (code "43") (name "Net-(U4-VCC)") (class "Default")
      (node (ref "C17") (pin "1") (pinfunction "1_1") (pintype "passive"))
      (node (ref "U4") (pin "P28") (pinfunction "VCC_P28") (pintype "bidirectional"))
    )
    (net (code "44") (name "Net-(U4-VCOMH)") (class "Default")
      (node (ref "C19") (pin "1") (pinfunction "1_1") (pintype "passive"))
      (node (ref "U4") (pin "P27") (pinfunction "VCOMH_P27") (pintype "bidirectional"))
    )
    (net (code "45") (name "Net-(U9-CC1)") (class "Default")
      (node (ref "R6") (pin "1") (pinfunction "1_1") (pintype "passive"))
      (node (ref "U9") (pin "A5") (pinfunction "CC1_A5") (pintype "bidirectional"))
    )
    (net (code "46") (name "Net-(U9-CC2)") (class "Default")
      (node (ref "R7") (pin "1") (pinfunction "1_1") (pintype "passive"))
      (node (ref "U9") (pin "B5") (pinfunction "CC2_B5") (pintype "bidirectional"))
    )
    (net (code "47") (name "OLED_RST") (class "Default")
      (node (ref "ESP") (pin "50") (pinfunction "GPIO45_50") (pintype "bidirectional"))
      (node (ref "R20") (pin "1") (pinfunction "1_1") (pintype "passive"))
      (node (ref "U4") (pin "P14") (pinfunction "/RES_P14") (pintype "bidirectional"))
    )
    (net (code "48") (name "RX") (class "Default")
      (node (ref "ESP") (pin "49") (pinfunction "U0RXD_49") (pintype "bidirectional"))
    )
    (net (code "49") (name "SCL") (class "Default")
      (node (ref "ESP") (pin "39") (pinfunction "GPIO35_39") (pintype "bidirectional"))
      (node (ref "J2") (pin "4") (pinfunction "SCL_4") (pintype "passive"))
      (node (ref "R23") (pin "1") (pinfunction "1_1") (pintype "passive"))
      (node (ref "U4") (pin "P18") (pinfunction "D0/SPI_SCLK/I2C_SCK_P18") (pintype "bidirectional"))
    )
    (net (code "50") (name "SDA") (class "Default")
      (node (ref "ESP") (pin "37") (pinfunction "GPIO33_37") (pintype "bidirectional"))
      (node (ref "J2") (pin "3") (pinfunction "SDA_3") (pintype "passive"))
      (node (ref "R22") (pin "1") (pinfunction "1_1") (pintype "passive"))
      (node (ref "U4") (pin "P19") (pinfunction "D1/SPI_SDIN/I2C_SDA_P19") (pintype "bidirectional"))
      (node (ref "U4") (pin "P20") (pinfunction "D2/I2C_SDA_P20") (pintype "bidirectional"))
    )
    (net (code "51") (name "SERVO_SIG") (class "Default")
      (node (ref "ESP") (pin "8") (pinfunction "GPIO3_8") (pintype "bidirectional"))
      (node (ref "SERVO") (pin "1") (pinfunction "1_1") (pintype "passive"))
    )
    (net (code "52") (name "SSR1") (class "Default")
      (node (ref "ESP") (pin "6") (pinfunction "GPIO1_6") (pintype "bidirectional"))
      (node (ref "Q5") (pin "1") (pinfunction "G_1") (pintype "bidirectional"))
      (node (ref "R8") (pin "2") (pinfunction "2_2") (pintype "passive"))
    )
    (net (code "53") (name "SSR2") (class "Default")
      (node (ref "ESP") (pin "7") (pinfunction "GPIO2_7") (pintype "bidirectional"))
      (node (ref "Q4") (pin "1") (pinfunction "G_1") (pintype "bidirectional"))
      (node (ref "R4") (pin "2") (pinfunction "2_2") (pintype "passive"))
    )
    (net (code "54") (name "TX") (class "Default")
      (node (ref "ESP") (pin "48") (pinfunction "U0TXD_48") (pintype "bidirectional"))
    )
    (net (code "55") (name "VCC") (class "Default")
      (node (ref "-OUT+") (pin "1") (pinfunction "S_1") (pintype "passive"))
      (node (ref "C11") (pin "2") (pinfunction "2_2") (pintype "passive"))
      (node (ref "C13") (pin "2") (pinfunction "2_2") (pintype "passive"))
      (node (ref "D2") (pin "P$2") (pinfunction "C_P$2") (pintype "passive"))
      (node (ref "D4") (pin "P$2") (pinfunction "C_P$2") (pintype "passive"))
      (node (ref "JMP1") (pin "3") (pinfunction "3_3") (pintype "passive"))
      (node (ref "JMP2") (pin "3") (pinfunction "3_3") (pintype "passive"))
      (node (ref "OUT1") (pin "1") (pinfunction "S_1") (pintype "passive"))
      (node (ref "OUT2") (pin "1") (pinfunction "S_1") (pintype "passive"))
      (node (ref "SERVO") (pin "2") (pinfunction "2_2") (pintype "passive"))
      (node (ref "SSR1") (pin "1") (pinfunction "S_1") (pintype "passive"))
      (node (ref "SSR2") (pin "1") (pinfunction "S_1") (pintype "passive"))
      (node (ref "U8") (pin "3") (pinfunction "IN_3") (pintype "bidirectional"))
      (node (ref "VCC") (pin "1") (pinfunction "S_1") (pintype "passive"))
    )
    (net (code "56") (name "VPP") (class "Default")
      (node (ref "C1") (pin "2") (pinfunction "2_2") (pintype "passive"))
      (node (ref "U3") (pin "P1") (pinfunction "VIN_P1") (pintype "bidirectional"))
      (node (ref "U3") (pin "P3") (pinfunction "EN_P3") (pintype "bidirectional"))
      (node (ref "U9") (pin "A4B9") (pinfunction "VBUS_A4B9") (pintype "bidirectional"))
      (node (ref "U9") (pin "B4A9") (pinfunction "VBUS_B4A9") (pintype "bidirectional"))
    )
    (net (code "57") (name "unconnected-(B4-1-PadP$1)") (class "Default")
      (node (ref "B4") (pin "P$1") (pinfunction "1_P$1") (pintype "bidirectional"))
    )
    (net (code "58") (name "unconnected-(B4-4-PadP$3)") (class "Default")
      (node (ref "B4") (pin "P$3") (pinfunction "4_P$3") (pintype "bidirectional"))
    )
    (net (code "59") (name "unconnected-(B5-1-PadP$1)") (class "Default")
      (node (ref "B5") (pin "P$1") (pinfunction "1_P$1") (pintype "bidirectional"))
    )
    (net (code "60") (name "unconnected-(B5-4-PadP$3)") (class "Default")
      (node (ref "B5") (pin "P$3") (pinfunction "4_P$3") (pintype "bidirectional"))
    )
    (net (code "61") (name "unconnected-(B6-1-PadP$1)") (class "Default")
      (node (ref "B6") (pin "P$1") (pinfunction "1_P$1") (pintype "bidirectional"))
    )
    (net (code "62") (name "unconnected-(B6-4-PadP$3)") (class "Default")
      (node (ref "B6") (pin "P$3") (pinfunction "4_P$3") (pintype "bidirectional"))
    )
    (net (code "63") (name "unconnected-(ESP-DAC_1-Pad23)") (class "Default")
      (node (ref "ESP") (pin "23") (pinfunction "DAC_1_23") (pintype "bidirectional"))
    )
    (net (code "64") (name "unconnected-(ESP-GPIO4-Pad9)") (class "Default")
      (node (ref "ESP") (pin "9") (pinfunction "GPIO4_9") (pintype "bidirectional"))
    )
    (net (code "65") (name "unconnected-(ESP-GPIO8-Pad13)") (class "Default")
      (node (ref "ESP") (pin "13") (pinfunction "GPIO8_13") (pintype "bidirectional"))
    )
    (net (code "66") (name "unconnected-(ESP-GPIO10-Pad15)") (class "Default")
      (node (ref "ESP") (pin "15") (pinfunction "GPIO10_15") (pintype "bidirectional"))
    )
    (net (code "67") (name "unconnected-(ESP-GPIO14-Pad19)") (class "Default")
      (node (ref "ESP") (pin "19") (pinfunction "GPIO14_19") (pintype "bidirectional"))
    )
    (net (code "68") (name "unconnected-(ESP-GPIO21-Pad28)") (class "Default")
      (node (ref "ESP") (pin "28") (pinfunction "GPIO21_28") (pintype "bidirectional"))
    )
    (net (code "69") (name "unconnected-(ESP-GPIO34-Pad38)") (class "Default")
      (node (ref "ESP") (pin "38") (pinfunction "GPIO34_38") (pintype "bidirectional"))
    )
    (net (code "70") (name "unconnected-(ESP-GPIO46-Pad55)") (class "Default")
      (node (ref "ESP") (pin "55") (pinfunction "GPIO46_55") (pintype "bidirectional"))
    )
    (net (code "71") (name "unconnected-(ESP-MTDI-Pad46)") (class "Default")
      (node (ref "ESP") (pin "46") (pinfunction "MTDI_46") (pintype "bidirectional"))
    )
    (net (code "72") (name "unconnected-(ESP-MTMS-Pad47)") (class "Default")
      (node (ref "ESP") (pin "47") (pinfunction "MTMS_47") (pintype "bidirectional"))
    )
    (net (code "73") (name "unconnected-(ESP-SPICLK-Pad34)") (class "Default")
      (node (ref "ESP") (pin "34") (pinfunction "SPICLK_34") (pintype "bidirectional"))
    )
    (net (code "74") (name "unconnected-(ESP-SPICS0-Pad33)") (class "Default")
      (node (ref "ESP") (pin "33") (pinfunction "SPICS0_33") (pintype "bidirectional"))
    )
    (net (code "75") (name "unconnected-(ESP-SPICS1-Pad29)") (class "Default")
      (node (ref "ESP") (pin "29") (pinfunction "SPICS1_29") (pintype "bidirectional"))
    )
    (net (code "76") (name "unconnected-(ESP-SPID-Pad36)") (class "Default")
      (node (ref "ESP") (pin "36") (pinfunction "SPID_36") (pintype "bidirectional"))
    )
    (net (code "77") (name "unconnected-(ESP-SPIHD-Pad31)") (class "Default")
      (node (ref "ESP") (pin "31") (pinfunction "SPIHD_31") (pintype "bidirectional"))
    )
    (net (code "78") (name "unconnected-(ESP-SPIQ-Pad35)") (class "Default")
      (node (ref "ESP") (pin "35") (pinfunction "SPIQ_35") (pintype "bidirectional"))
    )
    (net (code "79") (name "unconnected-(ESP-SPIWP-Pad32)") (class "Default")
      (node (ref "ESP") (pin "32") (pinfunction "SPIWP_32") (pintype "bidirectional"))
    )
    (net (code "80") (name "unconnected-(ESP-VDD_SPI-Pad30)") (class "Default")
      (node (ref "ESP") (pin "30") (pinfunction "VDD_SPI_30") (pintype "bidirectional"))
    )
    (net (code "81") (name "unconnected-(ESP-XTAL_32K_N-Pad22)") (class "Default")
      (node (ref "ESP") (pin "22") (pinfunction "XTAL_32K_N_22") (pintype "bidirectional"))
    )
    (net (code "82") (name "unconnected-(GPIO0-2-PadP2)") (class "Default")
      (node (ref "GPIO0") (pin "P2") (pinfunction "2_P2") (pintype "bidirectional"))
    )
    (net (code "83") (name "unconnected-(GPIO0-3-PadP3)") (class "Default")
      (node (ref "GPIO0") (pin "P3") (pinfunction "3_P3") (pintype "bidirectional"))
    )
    (net (code "84") (name "unconnected-(L1-CLKO-PadP2)") (class "Default")
      (node (ref "L1") (pin "P2") (pinfunction "CLKO_P2") (pintype "bidirectional"))
    )
    (net (code "85") (name "unconnected-(L1-SDO-PadP3)") (class "Default")
      (node (ref "L1") (pin "P3") (pinfunction "SDO_P3") (pintype "bidirectional"))
    )
    (net (code "86") (name "unconnected-(RESET-2-PadP2)") (class "Default")
      (node (ref "RESET") (pin "P2") (pinfunction "2_P2") (pintype "bidirectional"))
    )
    (net (code "87") (name "unconnected-(RESET-3-PadP3)") (class "Default")
      (node (ref "RESET") (pin "P3") (pinfunction "3_P3") (pintype "bidirectional"))
    )
    (net (code "88") (name "unconnected-(U3-BP-PadP4)") (class "Default")
      (node (ref "U3") (pin "P4") (pinfunction "BP_P4") (pintype "bidirectional"))
    )
    (net (code "89") (name "unconnected-(U4-D3-PadP21)") (class "Default")
      (node (ref "U4") (pin "P21") (pinfunction "D3_P21") (pintype "bidirectional"))
    )
    (net (code "90") (name "unconnected-(U4-D4-PadP22)") (class "Default")
      (node (ref "U4") (pin "P22") (pinfunction "D4_P22") (pintype "bidirectional"))
    )
    (net (code "91") (name "unconnected-(U4-D5-PadP23)") (class "Default")
      (node (ref "U4") (pin "P23") (pinfunction "D5_P23") (pintype "bidirectional"))
    )
    (net (code "92") (name "unconnected-(U4-D6-PadP24)") (class "Default")
      (node (ref "U4") (pin "P24") (pinfunction "D6_P24") (pintype "bidirectional"))
    )
    (net (code "93") (name "unconnected-(U4-D7-PadP25)") (class "Default")
      (node (ref "U4") (pin "P25") (pinfunction "D7_P25") (pintype "bidirectional"))
    )
    (net (code "94") (name "unconnected-(U4-DC{slash}I2C_SA0-PadP15)") (class "Default")
      (node (ref "U4") (pin "P15") (pinfunction "DC/I2C_SA0_P15") (pintype "bidirectional"))
    )
    (net (code "95") (name "unconnected-(U4-E{slash}RD-PadP17)") (class "Default")
      (node (ref "U4") (pin "P17") (pinfunction "E/RD_P17") (pintype "bidirectional"))
    )
    (net (code "96") (name "unconnected-(U4-NC-PadP7)") (class "Default")
      (node (ref "U4") (pin "P7") (pinfunction "NC_P7") (pintype "bidirectional"))
    )
    (net (code "97") (name "unconnected-(U4-R{slash}W-PadP16)") (class "Default")
      (node (ref "U4") (pin "P16") (pinfunction "R/W_P16") (pintype "bidirectional"))
    )
    (net (code "98") (name "unconnected-(U4-{slash}CS-PadP13)") (class "Default")
      (node (ref "U4") (pin "P13") (pinfunction "/CS_P13") (pintype "bidirectional"))
    )
  )
)
